# Backpack_Panel.net
KiCad netlist of a schematic drawn in EAGLE
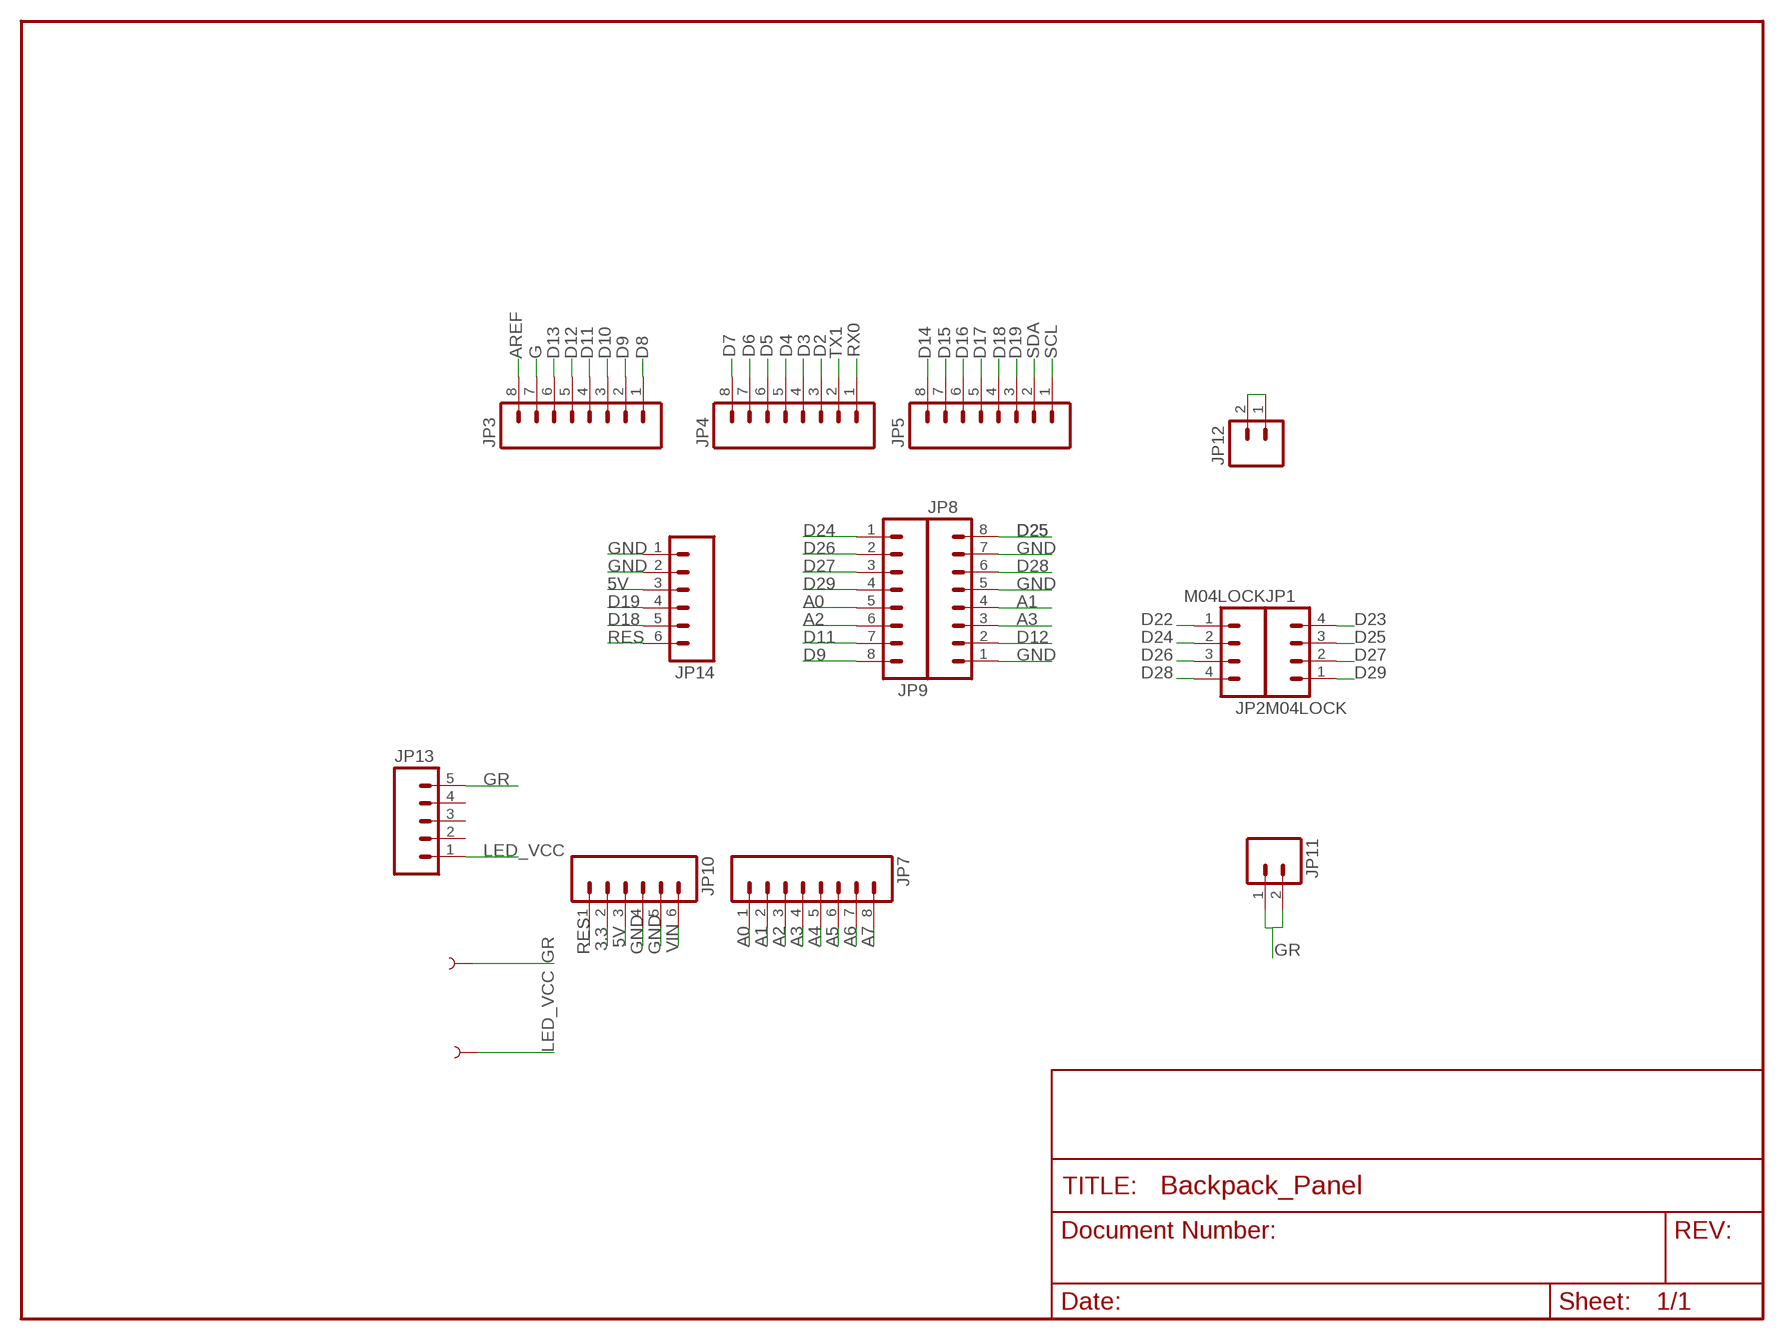
[diagram p0: schematic, sheet 1]

(export (version "E")
  (design (tool "Eeschema 10.0.6"))
  (components
    (comp (ref "JP1")
      (value "M04LOCK")
      (footprint "eagle-import:1X04_LOCK")
      (libsource (lib "eagle-import") (part "M04LOCK"))
    )
    (comp (ref "JP2")
      (value "M04LOCK")
      (footprint "eagle-import:1X04_LOCK")
      (libsource (lib "eagle-import") (part "M04LOCK"))
    )
    (comp (ref "JP3")
      (value "M08LOCK")
      (footprint "eagle-import:1X08_LOCK")
      (libsource (lib "eagle-import") (part "M08LOCK"))
    )
    (comp (ref "JP4")
      (value "M08LOCK")
      (footprint "eagle-import:1X08_LOCK")
      (libsource (lib "eagle-import") (part "M08LOCK"))
    )
    (comp (ref "JP5")
      (value "M08LOCK")
      (footprint "eagle-import:1X08_LOCK")
      (libsource (lib "eagle-import") (part "M08LOCK"))
    )
    (comp (ref "JP7")
      (value "M08LOCK")
      (footprint "eagle-import:1X08_LOCK")
      (libsource (lib "eagle-import") (part "M08LOCK"))
    )
    (comp (ref "JP8")
      (value "M08LOCK")
      (footprint "eagle-import:1X08_LOCK")
      (libsource (lib "eagle-import") (part "SparkFun-Connectors_M08LOCK"))
    )
    (comp (ref "JP9")
      (value "M08LOCK")
      (footprint "eagle-import:1X08_LOCK")
      (libsource (lib "eagle-import") (part "SparkFun-Connectors_M08LOCK"))
    )
    (comp (ref "JP10")
      (value "M06LOCK")
      (footprint "eagle-import:1X06_LOCK")
      (libsource (lib "eagle-import") (part "M06LOCK"))
    )
    (comp (ref "JP11")
      (value "M02LOCK")
      (footprint "eagle-import:1X02_LOCK")
      (libsource (lib "eagle-import") (part "M02LOCK"))
    )
    (comp (ref "JP12")
      (value "M02LOCK")
      (footprint "eagle-import:1X02_LOCK")
      (libsource (lib "eagle-import") (part "M02LOCK"))
    )
    (comp (ref "JP13")
      (value "M05LOCK")
      (footprint "eagle-import:1X05_LOCK")
      (libsource (lib "eagle-import") (part "M05LOCK"))
    )
    (comp (ref "JP14")
      (value "M06LOCK")
      (footprint "eagle-import:1X06_LOCK")
      (libsource (lib "eagle-import") (part "SparkFun-Connectors_M06LOCK"))
    )
    (comp (ref "U$1")
      (value "SEWTAP2")
      (footprint "eagle-import:PETAL-LONG-2")
      (libsource (lib "eagle-import") (part "SEWTAP2"))
    )
    (comp (ref "U$2")
      (value "SEWTAP2")
      (footprint "eagle-import:PETAL-LONG-2")
      (libsource (lib "eagle-import") (part "SEWTAP2"))
    )
  )
  (nets
    (net (code "1") (name "/3.3") (class "Default")
      (node (ref "JP10") (pin "2") (pinfunction "2_2") (pintype "passive"))
    )
    (net (code "2") (name "/5V") (class "Default")
      (node (ref "JP10") (pin "3") (pinfunction "3_3") (pintype "passive"))
      (node (ref "JP14") (pin "3") (pinfunction "3_3") (pintype "passive"))
    )
    (net (code "3") (name "/A0") (class "Default")
      (node (ref "JP7") (pin "1") (pinfunction "1_1") (pintype "passive"))
      (node (ref "JP9") (pin "5") (pinfunction "5_5") (pintype "passive"))
    )
    (net (code "4") (name "/A1") (class "Default")
      (node (ref "JP7") (pin "2") (pinfunction "2_2") (pintype "passive"))
      (node (ref "JP8") (pin "4") (pinfunction "4_4") (pintype "passive"))
    )
    (net (code "5") (name "/A2") (class "Default")
      (node (ref "JP7") (pin "3") (pinfunction "3_3") (pintype "passive"))
      (node (ref "JP9") (pin "6") (pinfunction "6_6") (pintype "passive"))
    )
    (net (code "6") (name "/A3") (class "Default")
      (node (ref "JP7") (pin "4") (pinfunction "4_4") (pintype "passive"))
      (node (ref "JP8") (pin "3") (pinfunction "3_3") (pintype "passive"))
    )
    (net (code "7") (name "/A4") (class "Default")
      (node (ref "JP7") (pin "5") (pinfunction "5_5") (pintype "passive"))
    )
    (net (code "8") (name "/A5") (class "Default")
      (node (ref "JP7") (pin "6") (pinfunction "6_6") (pintype "passive"))
    )
    (net (code "9") (name "/A6") (class "Default")
      (node (ref "JP7") (pin "7") (pinfunction "7_7") (pintype "passive"))
    )
    (net (code "10") (name "/A7") (class "Default")
      (node (ref "JP7") (pin "8") (pinfunction "8_8") (pintype "passive"))
    )
    (net (code "11") (name "/AREF") (class "Default")
      (node (ref "JP3") (pin "8") (pinfunction "8_8") (pintype "passive"))
    )
    (net (code "12") (name "/D2") (class "Default")
      (node (ref "JP4") (pin "3") (pinfunction "3_3") (pintype "passive"))
    )
    (net (code "13") (name "/D3") (class "Default")
      (node (ref "JP4") (pin "4") (pinfunction "4_4") (pintype "passive"))
    )
    (net (code "14") (name "/D4") (class "Default")
      (node (ref "JP4") (pin "5") (pinfunction "5_5") (pintype "passive"))
    )
    (net (code "15") (name "/D5") (class "Default")
      (node (ref "JP4") (pin "6") (pinfunction "6_6") (pintype "passive"))
    )
    (net (code "16") (name "/D6") (class "Default")
      (node (ref "JP4") (pin "7") (pinfunction "7_7") (pintype "passive"))
    )
    (net (code "17") (name "/D7") (class "Default")
      (node (ref "JP4") (pin "8") (pinfunction "8_8") (pintype "passive"))
    )
    (net (code "18") (name "/D8") (class "Default")
      (node (ref "JP3") (pin "1") (pinfunction "1_1") (pintype "passive"))
    )
    (net (code "19") (name "/D9") (class "Default")
      (node (ref "JP3") (pin "2") (pinfunction "2_2") (pintype "passive"))
      (node (ref "JP9") (pin "8") (pinfunction "8_8") (pintype "passive"))
    )
    (net (code "20") (name "/D10") (class "Default")
      (node (ref "JP3") (pin "3") (pinfunction "3_3") (pintype "passive"))
    )
    (net (code "21") (name "/D11") (class "Default")
      (node (ref "JP3") (pin "4") (pinfunction "4_4") (pintype "passive"))
      (node (ref "JP9") (pin "7") (pinfunction "7_7") (pintype "passive"))
    )
    (net (code "22") (name "/D12") (class "Default")
      (node (ref "JP3") (pin "5") (pinfunction "5_5") (pintype "passive"))
      (node (ref "JP8") (pin "2") (pinfunction "2_2") (pintype "passive"))
    )
    (net (code "23") (name "/D13") (class "Default")
      (node (ref "JP3") (pin "6") (pinfunction "6_6") (pintype "passive"))
    )
    (net (code "24") (name "/D14") (class "Default")
      (node (ref "JP5") (pin "8") (pinfunction "8_8") (pintype "passive"))
    )
    (net (code "25") (name "/D15") (class "Default")
      (node (ref "JP5") (pin "7") (pinfunction "7_7") (pintype "passive"))
    )
    (net (code "26") (name "/D16") (class "Default")
      (node (ref "JP5") (pin "6") (pinfunction "6_6") (pintype "passive"))
    )
    (net (code "27") (name "/D17") (class "Default")
      (node (ref "JP5") (pin "5") (pinfunction "5_5") (pintype "passive"))
    )
    (net (code "28") (name "/D18") (class "Default")
      (node (ref "JP14") (pin "5") (pinfunction "5_5") (pintype "passive"))
      (node (ref "JP5") (pin "4") (pinfunction "4_4") (pintype "passive"))
    )
    (net (code "29") (name "/D19") (class "Default")
      (node (ref "JP14") (pin "4") (pinfunction "4_4") (pintype "passive"))
      (node (ref "JP5") (pin "3") (pinfunction "3_3") (pintype "passive"))
    )
    (net (code "30") (name "/D22") (class "Default")
      (node (ref "JP2") (pin "1") (pinfunction "1_1") (pintype "passive"))
    )
    (net (code "31") (name "/D23") (class "Default")
      (node (ref "JP1") (pin "4") (pinfunction "4_4") (pintype "passive"))
    )
    (net (code "32") (name "/D24") (class "Default")
      (node (ref "JP2") (pin "2") (pinfunction "2_2") (pintype "passive"))
      (node (ref "JP9") (pin "1") (pinfunction "1_1") (pintype "passive"))
    )
    (net (code "33") (name "/D25") (class "Default")
      (node (ref "JP1") (pin "3") (pinfunction "3_3") (pintype "passive"))
      (node (ref "JP8") (pin "8") (pinfunction "8_8") (pintype "passive"))
    )
    (net (code "34") (name "/D26") (class "Default")
      (node (ref "JP2") (pin "3") (pinfunction "3_3") (pintype "passive"))
      (node (ref "JP9") (pin "2") (pinfunction "2_2") (pintype "passive"))
    )
    (net (code "35") (name "/D27") (class "Default")
      (node (ref "JP1") (pin "2") (pinfunction "2_2") (pintype "passive"))
      (node (ref "JP9") (pin "3") (pinfunction "3_3") (pintype "passive"))
    )
    (net (code "36") (name "/D28") (class "Default")
      (node (ref "JP2") (pin "4") (pinfunction "4_4") (pintype "passive"))
      (node (ref "JP8") (pin "6") (pinfunction "6_6") (pintype "passive"))
    )
    (net (code "37") (name "/D29") (class "Default")
      (node (ref "JP1") (pin "1") (pinfunction "1_1") (pintype "passive"))
      (node (ref "JP9") (pin "4") (pinfunction "4_4") (pintype "passive"))
    )
    (net (code "38") (name "/G") (class "Default")
      (node (ref "JP3") (pin "7") (pinfunction "7_7") (pintype "passive"))
    )
    (net (code "39") (name "/GND") (class "Default")
      (node (ref "JP10") (pin "4") (pinfunction "4_4") (pintype "passive"))
      (node (ref "JP10") (pin "5") (pinfunction "5_5") (pintype "passive"))
      (node (ref "JP14") (pin "1") (pinfunction "1_1") (pintype "passive"))
      (node (ref "JP14") (pin "2") (pinfunction "2_2") (pintype "passive"))
      (node (ref "JP8") (pin "1") (pinfunction "1_1") (pintype "passive"))
      (node (ref "JP8") (pin "5") (pinfunction "5_5") (pintype "passive"))
      (node (ref "JP8") (pin "7") (pinfunction "7_7") (pintype "passive"))
    )
    (net (code "40") (name "/GR") (class "Default")
      (node (ref "JP11") (pin "1") (pinfunction "1_1") (pintype "passive"))
      (node (ref "JP11") (pin "2") (pinfunction "2_2") (pintype "passive"))
      (node (ref "JP13") (pin "5") (pinfunction "5_5") (pintype "passive"))
      (node (ref "U$1") (pin "1") (pinfunction "1_1") (pintype "bidirectional"))
    )
    (net (code "41") (name "/LED_VCC") (class "Default")
      (node (ref "JP13") (pin "1") (pinfunction "1_1") (pintype "passive"))
      (node (ref "U$2") (pin "1") (pinfunction "1_1") (pintype "bidirectional"))
    )
    (net (code "42") (name "/RES") (class "Default")
      (node (ref "JP10") (pin "1") (pinfunction "1_1") (pintype "passive"))
      (node (ref "JP14") (pin "6") (pinfunction "6_6") (pintype "passive"))
    )
    (net (code "43") (name "/RX0") (class "Default")
      (node (ref "JP4") (pin "1") (pinfunction "1_1") (pintype "passive"))
    )
    (net (code "44") (name "/SCL") (class "Default")
      (node (ref "JP5") (pin "1") (pinfunction "1_1") (pintype "passive"))
    )
    (net (code "45") (name "/SDA") (class "Default")
      (node (ref "JP5") (pin "2") (pinfunction "2_2") (pintype "passive"))
    )
    (net (code "46") (name "/TX1") (class "Default")
      (node (ref "JP4") (pin "2") (pinfunction "2_2") (pintype "passive"))
    )
    (net (code "47") (name "/VIN") (class "Default")
      (node (ref "JP10") (pin "6") (pinfunction "6_6") (pintype "passive"))
    )
    (net (code "48") (name "Net-(JP12-Pad1)") (class "Default")
      (node (ref "JP12") (pin "1") (pinfunction "1_1") (pintype "passive"))
      (node (ref "JP12") (pin "2") (pinfunction "2_2") (pintype "passive"))
    )
    (net (code "49") (name "unconnected-(JP13-Pad2)") (class "Default")
      (node (ref "JP13") (pin "2") (pinfunction "2_2") (pintype "passive"))
    )
    (net (code "50") (name "unconnected-(JP13-Pad3)") (class "Default")
      (node (ref "JP13") (pin "3") (pinfunction "3_3") (pintype "passive"))
    )
    (net (code "51") (name "unconnected-(JP13-Pad4)") (class "Default")
      (node (ref "JP13") (pin "4") (pinfunction "4_4") (pintype "passive"))
    )
  )
)
